# splitter.net
KiCad netlist of a schematic drawn in EAGLE
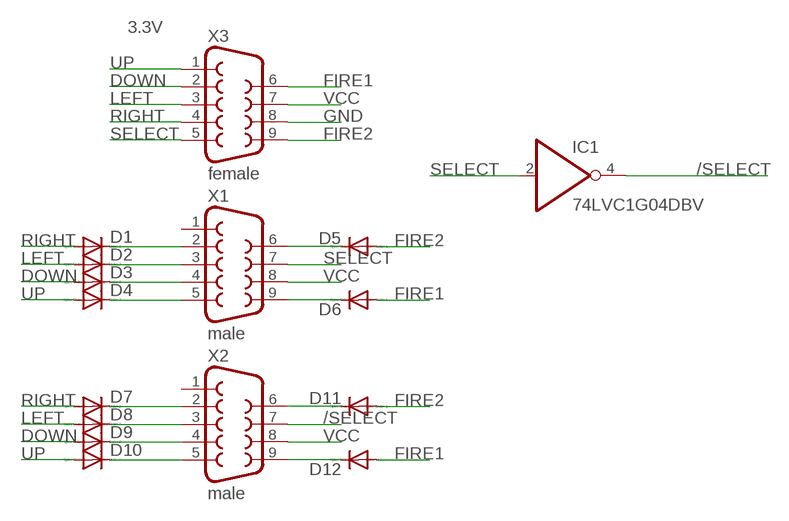
[diagram p0: schematic, sheet 1]

(export (version "E")
  (design (tool "Eeschema 10.0.6"))
  (components
    (comp (ref "D1")
      (value "DIODE-SOD323-R")
      (footprint "eagle-import:SOD323-R")
      (libsource (lib "eagle-import") (part "DIODE-SOD323-R"))
    )
    (comp (ref "D2")
      (value "DIODE-SOD323-R")
      (footprint "eagle-import:SOD323-R")
      (libsource (lib "eagle-import") (part "DIODE-SOD323-R"))
    )
    (comp (ref "D3")
      (value "DIODE-SOD323-R")
      (footprint "eagle-import:SOD323-R")
      (libsource (lib "eagle-import") (part "DIODE-SOD323-R"))
    )
    (comp (ref "D4")
      (value "DIODE-SOD323-R")
      (footprint "eagle-import:SOD323-R")
      (libsource (lib "eagle-import") (part "DIODE-SOD323-R"))
    )
    (comp (ref "D5")
      (value "DIODE-SOD323-R")
      (footprint "eagle-import:SOD323-R")
      (libsource (lib "eagle-import") (part "DIODE-SOD323-R"))
    )
    (comp (ref "D6")
      (value "DIODE-SOD323-R")
      (footprint "eagle-import:SOD323-R")
      (libsource (lib "eagle-import") (part "DIODE-SOD323-R"))
    )
    (comp (ref "D7")
      (value "DIODE-SOD323-R")
      (footprint "eagle-import:SOD323-R")
      (libsource (lib "eagle-import") (part "DIODE-SOD323-R"))
    )
    (comp (ref "D8")
      (value "DIODE-SOD323-R")
      (footprint "eagle-import:SOD323-R")
      (libsource (lib "eagle-import") (part "DIODE-SOD323-R"))
    )
    (comp (ref "D9")
      (value "DIODE-SOD323-R")
      (footprint "eagle-import:SOD323-R")
      (libsource (lib "eagle-import") (part "DIODE-SOD323-R"))
    )
    (comp (ref "D10")
      (value "DIODE-SOD323-R")
      (footprint "eagle-import:SOD323-R")
      (libsource (lib "eagle-import") (part "DIODE-SOD323-R"))
    )
    (comp (ref "D11")
      (value "DIODE-SOD323-R")
      (footprint "eagle-import:SOD323-R")
      (libsource (lib "eagle-import") (part "DIODE-SOD323-R"))
    )
    (comp (ref "D12")
      (value "DIODE-SOD323-R")
      (footprint "eagle-import:SOD323-R")
      (libsource (lib "eagle-import") (part "DIODE-SOD323-R"))
    )
    (comp (ref "IC1")
      (value "74LVC1G04DBV")
      (footprint "eagle-import:SOT23-5")
      (libsource (lib "eagle-import") (part "741G04DBVLVC"))
    )
    (comp (ref "X1")
      (value "male")
      (footprint "eagle-import:F09D")
      (libsource (lib "eagle-import") (part "F09D"))
    )
    (comp (ref "X2")
      (value "male")
      (footprint "eagle-import:F09D")
      (libsource (lib "eagle-import") (part "F09D"))
    )
    (comp (ref "X3")
      (value "female")
      (footprint "eagle-import:F09D")
      (libsource (lib "eagle-import") (part "F09D"))
    )
  )
  (nets
    (net (code "2") (name "/DOWN") (class "Default")
      (node (ref "D3") (pin "A") (pinfunction "A_A") (pintype "passive"))
      (node (ref "D9") (pin "A") (pinfunction "A_A") (pintype "passive"))
      (node (ref "X3") (pin "2") (pinfunction "2_2") (pintype "passive"))
    )
    (net (code "3") (name "/FIRE1") (class "Default")
      (node (ref "D12") (pin "A") (pinfunction "A_A") (pintype "passive"))
      (node (ref "D6") (pin "A") (pinfunction "A_A") (pintype "passive"))
      (node (ref "X3") (pin "6") (pinfunction "6_6") (pintype "passive"))
    )
    (net (code "4") (name "/FIRE2") (class "Default")
      (node (ref "D11") (pin "A") (pinfunction "A_A") (pintype "passive"))
      (node (ref "D5") (pin "A") (pinfunction "A_A") (pintype "passive"))
      (node (ref "X3") (pin "9") (pinfunction "9_9") (pintype "passive"))
    )
    (net (code "5") (name "/GND") (class "Default")
      (node (ref "X3") (pin "8") (pinfunction "8_8") (pintype "passive"))
    )
    (net (code "6") (name "/LEFT") (class "Default")
      (node (ref "D2") (pin "A") (pinfunction "A_A") (pintype "passive"))
      (node (ref "D8") (pin "A") (pinfunction "A_A") (pintype "passive"))
      (node (ref "X3") (pin "3") (pinfunction "3_3") (pintype "passive"))
    )
    (net (code "7") (name "/RIGHT") (class "Default")
      (node (ref "D1") (pin "A") (pinfunction "A_A") (pintype "passive"))
      (node (ref "D7") (pin "A") (pinfunction "A_A") (pintype "passive"))
      (node (ref "X3") (pin "4") (pinfunction "4_4") (pintype "passive"))
    )
    (net (code "8") (name "/SELECT") (class "Default")
      (node (ref "IC1") (pin "2") (pinfunction "I_2") (pintype "input"))
      (node (ref "X1") (pin "7") (pinfunction "7_7") (pintype "passive"))
      (node (ref "X3") (pin "5") (pinfunction "5_5") (pintype "passive"))
    )
    (net (code "9") (name "/UP") (class "Default")
      (node (ref "D10") (pin "A") (pinfunction "A_A") (pintype "passive"))
      (node (ref "D4") (pin "A") (pinfunction "A_A") (pintype "passive"))
      (node (ref "X3") (pin "1") (pinfunction "1_1") (pintype "passive"))
    )
    (net (code "10") (name "/VCC") (class "Default")
      (node (ref "X1") (pin "8") (pinfunction "8_8") (pintype "passive"))
      (node (ref "X2") (pin "8") (pinfunction "8_8") (pintype "passive"))
      (node (ref "X3") (pin "7") (pinfunction "7_7") (pintype "passive"))
    )
    (net (code "11") (name "/{slash}SELECT") (class "Default")
      (node (ref "IC1") (pin "4") (pinfunction "O_4") (pintype "output"))
      (node (ref "X2") (pin "7") (pinfunction "7_7") (pintype "passive"))
    )
    (net (code "12") (name "Net-(D1-PadC)") (class "Default")
      (node (ref "D1") (pin "C") (pinfunction "C_C") (pintype "passive"))
      (node (ref "X1") (pin "2") (pinfunction "2_2") (pintype "passive"))
    )
    (net (code "13") (name "Net-(D2-PadC)") (class "Default")
      (node (ref "D2") (pin "C") (pinfunction "C_C") (pintype "passive"))
      (node (ref "X1") (pin "3") (pinfunction "3_3") (pintype "passive"))
    )
    (net (code "14") (name "Net-(D3-PadC)") (class "Default")
      (node (ref "D3") (pin "C") (pinfunction "C_C") (pintype "passive"))
      (node (ref "X1") (pin "4") (pinfunction "4_4") (pintype "passive"))
    )
    (net (code "15") (name "Net-(D4-PadC)") (class "Default")
      (node (ref "D4") (pin "C") (pinfunction "C_C") (pintype "passive"))
      (node (ref "X1") (pin "5") (pinfunction "5_5") (pintype "passive"))
    )
    (net (code "16") (name "Net-(D5-PadC)") (class "Default")
      (node (ref "D5") (pin "C") (pinfunction "C_C") (pintype "passive"))
      (node (ref "X1") (pin "6") (pinfunction "6_6") (pintype "passive"))
    )
    (net (code "17") (name "Net-(D6-PadC)") (class "Default")
      (node (ref "D6") (pin "C") (pinfunction "C_C") (pintype "passive"))
      (node (ref "X1") (pin "9") (pinfunction "9_9") (pintype "passive"))
    )
    (net (code "18") (name "Net-(D7-PadC)") (class "Default")
      (node (ref "D7") (pin "C") (pinfunction "C_C") (pintype "passive"))
      (node (ref "X2") (pin "2") (pinfunction "2_2") (pintype "passive"))
    )
    (net (code "19") (name "Net-(D8-PadC)") (class "Default")
      (node (ref "D8") (pin "C") (pinfunction "C_C") (pintype "passive"))
      (node (ref "X2") (pin "3") (pinfunction "3_3") (pintype "passive"))
    )
    (net (code "20") (name "Net-(D9-PadC)") (class "Default")
      (node (ref "D9") (pin "C") (pinfunction "C_C") (pintype "passive"))
      (node (ref "X2") (pin "4") (pinfunction "4_4") (pintype "passive"))
    )
    (net (code "21") (name "Net-(D10-PadC)") (class "Default")
      (node (ref "D10") (pin "C") (pinfunction "C_C") (pintype "passive"))
      (node (ref "X2") (pin "5") (pinfunction "5_5") (pintype "passive"))
    )
    (net (code "22") (name "Net-(D11-PadC)") (class "Default")
      (node (ref "D11") (pin "C") (pinfunction "C_C") (pintype "passive"))
      (node (ref "X2") (pin "6") (pinfunction "6_6") (pintype "passive"))
    )
    (net (code "23") (name "Net-(D12-PadC)") (class "Default")
      (node (ref "D12") (pin "C") (pinfunction "C_C") (pintype "passive"))
      (node (ref "X2") (pin "9") (pinfunction "9_9") (pintype "passive"))
    )
    (net (code "24") (name "unconnected-(X1-Pad1)") (class "Default")
      (node (ref "X1") (pin "1") (pinfunction "1_1") (pintype "passive"))
    )
    (net (code "25") (name "unconnected-(X2-Pad1)") (class "Default")
      (node (ref "X2") (pin "1") (pinfunction "1_1") (pintype "passive"))
    )
  )
)
